# driver_y_convertidor.net
KiCad netlist of a schematic drawn in Altium Designer
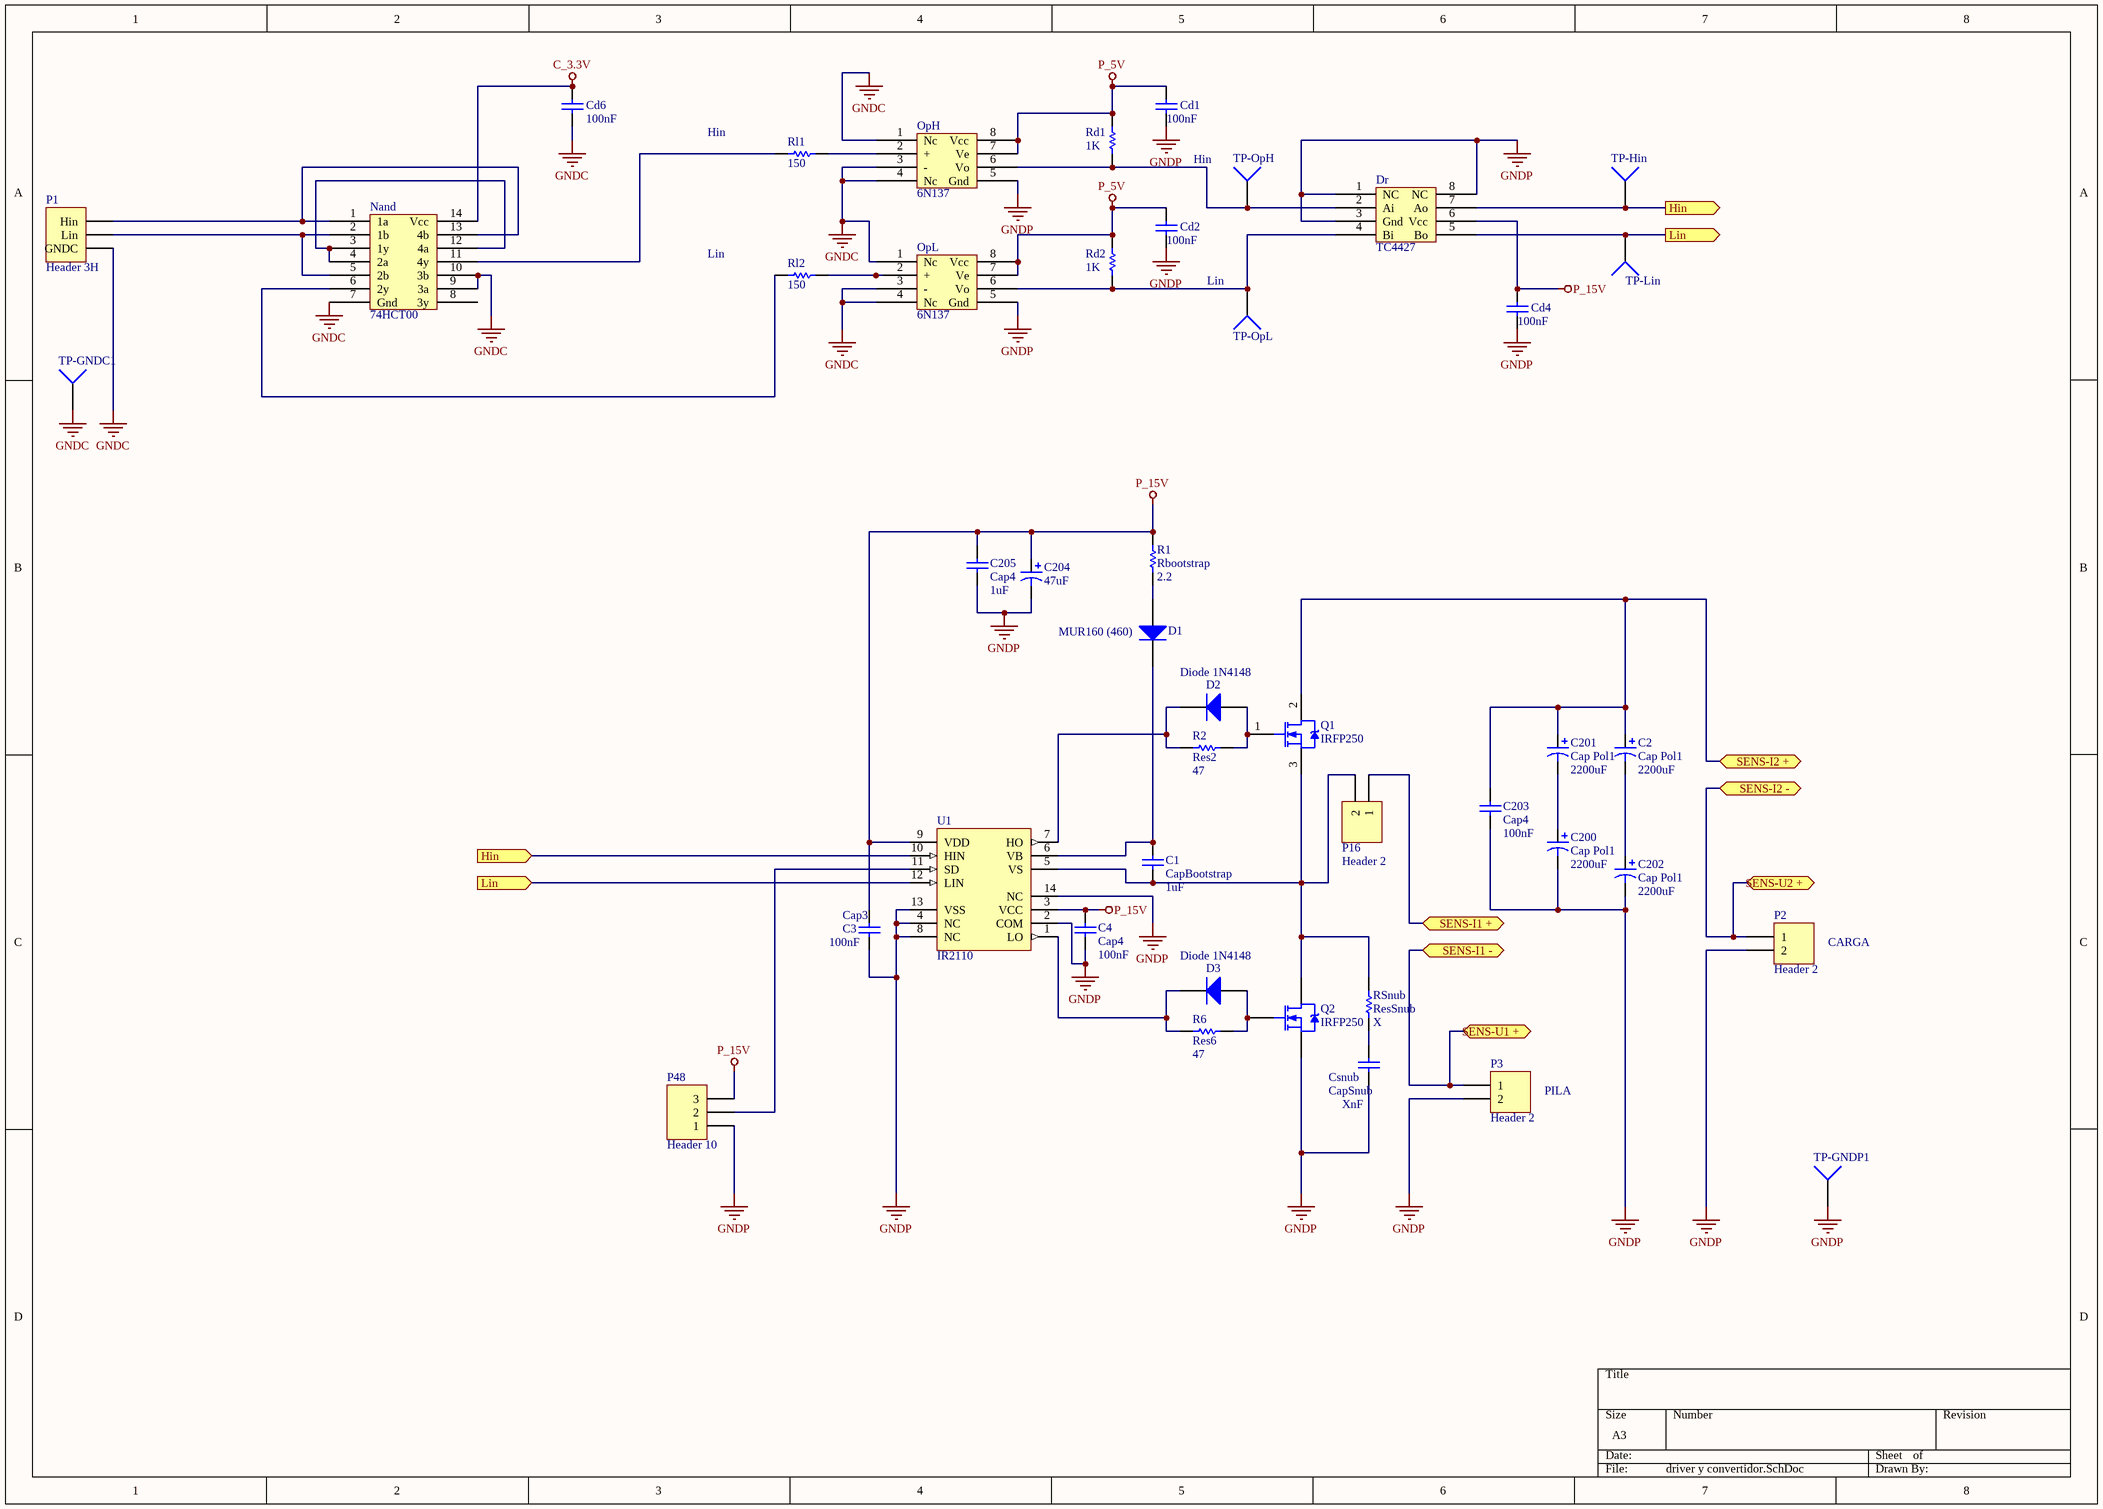
[diagram p0: driver y convertidor.SchDoc]

(export (version "E")
  (design (tool "Eeschema 10.0.6"))
  (components
    (comp (ref "C1")
      (value "CapBootstrap")
      (footprint "RAD-0.1")
      (description "THRU MULTICAPA 50V")
      (fields (field (name "ALTIUM_VALUE") "1uF") (field (name "PUBLISHER") "Altium Limited"))
      (libsource (lib "Miscellaneous Devices") (part "Cap"))
    )
    (comp (ref "C2")
      (value "Cap Pol1")
      (footprint "RB12.7-25*")
      (description "Polarized Capacitor (Radial)")
      (fields (field (name "ALTIUM_VALUE") "2200uF") (field (name "PUBLISHER") "Altium Limited"))
      (libsource (lib "Miscellaneous Devices") (part "Cap Pol1"))
    )
    (comp (ref "C3")
      (value "Cap3")
      (footprint "8-1206")
      (description "SMD MULTICAPA 50V")
      (fields (field (name "ALTIUM_VALUE") "100nF") (field (name "PUBLISHER") "Altium Limited"))
      (libsource (lib "Miscellaneous Devices") (part "Cap"))
    )
    (comp (ref "C4")
      (value "Cap4")
      (footprint "8-1206")
      (description "SMD MULTICAPA 50V")
      (fields (field (name "ALTIUM_VALUE") "100nF") (field (name "PUBLISHER") "Altium Limited"))
      (libsource (lib "Miscellaneous Devices") (part "Cap"))
    )
    (comp (ref "C200")
      (value "Cap Pol1")
      (footprint "RB12.7-25*")
      (description "Polarized Capacitor (Radial)")
      (fields (field (name "ALTIUM_VALUE") "2200uF") (field (name "PUBLISHER") "Altium Limited"))
      (libsource (lib "Miscellaneous Devices") (part "Cap Pol1"))
    )
    (comp (ref "C201")
      (value "Cap Pol1")
      (footprint "RB12.7-25*")
      (description "Polarized Capacitor (Radial)")
      (fields (field (name "ALTIUM_VALUE") "2200uF") (field (name "PUBLISHER") "Altium Limited"))
      (libsource (lib "Miscellaneous Devices") (part "Cap Pol1"))
    )
    (comp (ref "C202")
      (value "Cap Pol1")
      (footprint "RB12.7-25*")
      (description "Polarized Capacitor (Radial)")
      (fields (field (name "ALTIUM_VALUE") "2200uF") (field (name "PUBLISHER") "Altium Limited"))
      (libsource (lib "Miscellaneous Devices") (part "Cap Pol1"))
    )
    (comp (ref "C203")
      (value "Cap4")
      (footprint "8-1206")
      (description "SMD MULTICAPA 50V")
      (fields (field (name "ALTIUM_VALUE") "100nF") (field (name "PUBLISHER") "Altium Limited"))
      (libsource (lib "Miscellaneous Devices") (part "Cap"))
    )
    (comp (ref "C204")
      (value "47uF")
      (footprint "RB5.8-6.4*")
      (description "Polarized Capacitor (Radial)")
      (fields (field (name "Comment") "Cap Pol1") (field (name "PUBLISHER") "Altium Limited"))
      (libsource (lib "Miscellaneous Devices") (part "Cap Pol1"))
    )
    (comp (ref "C205")
      (value "Cap4")
      (footprint "8-1206")
      (description "SMD MULTICAPA 50V")
      (fields (field (name "ALTIUM_VALUE") "1uF") (field (name "PUBLISHER") "Altium Limited"))
      (libsource (lib "Miscellaneous Devices") (part "Cap"))
    )
    (comp (ref "Cd1")
      (value "100nF")
      (footprint "8-1206")
      (description "SMD MULTICAPA 50V")
      (fields (field (name "Comment") "Capd1") (field (name "PUBLISHER") "Altium Limited"))
      (libsource (lib "Miscellaneous Devices") (part "Cap"))
    )
    (comp (ref "Cd2")
      (value "100nF")
      (footprint "8-1206")
      (description "SMD MULTICAPA 50V")
      (fields (field (name "Comment") "Capd2") (field (name "PUBLISHER") "Altium Limited"))
      (libsource (lib "Miscellaneous Devices") (part "Cap"))
    )
    (comp (ref "Cd4")
      (value "100nF")
      (footprint "8-1206")
      (description "SMD MULTICAPA 50V")
      (fields (field (name "Comment") "Capd2") (field (name "PUBLISHER") "Altium Limited"))
      (libsource (lib "Miscellaneous Devices") (part "Cap"))
    )
    (comp (ref "Cd6")
      (value "100nF")
      (footprint "8-1206")
      (description "SMD MULTICAPA 50V")
      (fields (field (name "Comment") "Capd2") (field (name "PUBLISHER") "Altium Limited"))
      (libsource (lib "Miscellaneous Devices") (part "Cap"))
    )
    (comp (ref "Csnub")
      (value "CapSnub")
      (footprint "FootSnub")
      (description "SMD MULTICAPA 50V")
      (fields (field (name "ALTIUM_VALUE") "XnF") (field (name "PUBLISHER") "Altium Limited"))
      (libsource (lib "Miscellaneous Devices") (part "Cap"))
    )
    (comp (ref "D1")
      (value "MUR160 (460)")
      (footprint "CASE 267*")
      (description "THRU")
      (fields (field (name "PUBLISHER") "Altium Limited"))
      (libsource (lib "Miscellaneous Devices") (part "Diode 1N4007"))
    )
    (comp (ref "D2")
      (value "Diode 1N4148")
      (footprint "DO-35")
      (description "THRU")
      (fields (field (name "PUBLISHER") "Altium Limited"))
      (libsource (lib "Miscellaneous Devices") (part "Diode 1N4148"))
    )
    (comp (ref "D3")
      (value "Diode 1N4148")
      (footprint "DO-35")
      (description "THRU")
      (fields (field (name "PUBLISHER") "Altium Limited"))
      (libsource (lib "Miscellaneous Devices") (part "Diode 1N4148"))
    )
    (comp (ref "Dr") (value "TC4427") (footprint "TC4424-DIP8") (libsource (lib "Sensores") (part "TC4427")))
    (comp (ref "Nand")
      (value "74HCT00")
      (footprint "MM74HC00_GON")
      (libsource (lib "Sensores") (part "74HCT00"))
    )
    (comp (ref "OpH") (value "6N137") (footprint "6n137") (libsource (lib "Sensores") (part "6N137")))
    (comp (ref "OpL") (value "6N137") (footprint "6n137") (libsource (lib "Sensores") (part "6N137")))
    (comp (ref "P1")
      (value "Header 3H")
      (footprint "HDR1X3H*")
      (description "Header, 3-Pin, Right Angle")
      (fields (field (name "PUBLISHER") "Altium Limited"))
      (libsource (lib "Miscellaneous Connectors") (part "Header 3H"))
    )
    (comp (ref "P2")
      (value "Header 2")
      (footprint "HDR1X2-POT*")
      (description "Header, 2-Pin")
      (fields (field (name "PUBLISHER") "Altium Limited"))
      (libsource (lib "Miscellaneous Connectors") (part "Header 2"))
    )
    (comp (ref "P3")
      (value "Header 2")
      (footprint "Ind-Conector")
      (description "Header, 2-Pin")
      (fields (field (name "PUBLISHER") "Altium Limited"))
      (libsource (lib "Miscellaneous Connectors") (part "Header 2"))
    )
    (comp (ref "P16")
      (value "Header 2")
      (footprint "Ind-Conector")
      (description "Header, 2-Pin")
      (fields (field (name "PUBLISHER") "Altium Limited"))
      (libsource (lib "") (part "Header 2_1"))
    )
    (comp (ref "P48")
      (value "Header 10")
      (footprint "HDR1X3*")
      (description "Header, 3-Pin")
      (fields (field (name "PUBLISHER") "Altium Limited"))
      (libsource (lib "Miscellaneous Connectors") (part "Header 3"))
    )
    (comp (ref "Q1")
      (value "IRFP250")
      (footprint "TO-247AC")
      (description "HEXFET Power MOSFET")
      (fields (field (name "PUBLISHER") "Altium Limited"))
      (libsource (lib "") (part "IRFP250_1"))
    )
    (comp (ref "Q2")
      (value "IRFP250")
      (footprint "TO-247AC")
      (description "HEXFET Power MOSFET")
      (fields (field (name "PUBLISHER") "Altium Limited"))
      (libsource (lib "IR Discrete MOSFET - Power") (part "IRFP250"))
    )
    (comp (ref "R1")
      (value "Rbootstrap")
      (footprint "8-1206")
      (description "SMD 1206")
      (fields (field (name "ALTIUM_VALUE") "2.2") (field (name "PUBLISHER") "Altium Limited"))
      (libsource (lib "Miscellaneous Devices") (part "Res1"))
    )
    (comp (ref "R2")
      (value "Res2")
      (footprint "8-1206")
      (description "SMD 1206")
      (fields (field (name "ALTIUM_VALUE") "47") (field (name "PUBLISHER") "Altium Limited"))
      (libsource (lib "Miscellaneous Devices") (part "Res1"))
    )
    (comp (ref "R6")
      (value "Res6")
      (footprint "8-1206")
      (description "SMD 1206")
      (fields (field (name "ALTIUM_VALUE") "47") (field (name "PUBLISHER") "Altium Limited"))
      (libsource (lib "Miscellaneous Devices") (part "Res1"))
    )
    (comp (ref "Rd1")
      (value "1K")
      (footprint "8-1206")
      (description "SMD 1206")
      (fields (field (name "Comment") "Rd1") (field (name "PUBLISHER") "Altium Limited"))
      (libsource (lib "Miscellaneous Devices") (part "Res1"))
    )
    (comp (ref "Rd2")
      (value "1K")
      (footprint "8-1206")
      (description "SMD 1206")
      (fields (field (name "Comment") "Rd2") (field (name "PUBLISHER") "Altium Limited"))
      (libsource (lib "Miscellaneous Devices") (part "Res1"))
    )
    (comp (ref "Rl1")
      (value "150")
      (footprint "8-1206")
      (description "SMD 1206")
      (fields (field (name "Comment") "Rd1") (field (name "PUBLISHER") "Altium Limited"))
      (libsource (lib "Miscellaneous Devices") (part "Res1"))
    )
    (comp (ref "Rl2")
      (value "150")
      (footprint "8-1206")
      (description "SMD 1206")
      (fields (field (name "Comment") "Rd1") (field (name "PUBLISHER") "Altium Limited"))
      (libsource (lib "Miscellaneous Devices") (part "Res1"))
    )
    (comp (ref "RSnub")
      (value "ResSnub")
      (footprint "FootSnub")
      (description "SMD 1206")
      (fields (field (name "ALTIUM_VALUE") "X") (field (name "PUBLISHER") "Altium Limited"))
      (libsource (lib "Miscellaneous Devices") (part "Res1"))
    )
    (comp (ref "TP-GNDC1")
      (value "~")
      (footprint "PIN1")
      (description "Socket")
      (fields (field (name "PUBLISHER") "Altium Limited"))
      (libsource (lib "Miscellaneous Connectors") (part "Socket"))
    )
    (comp (ref "TP-GNDP1")
      (value "~")
      (footprint "PIN1")
      (description "Socket")
      (fields (field (name "PUBLISHER") "Altium Limited"))
      (libsource (lib "Miscellaneous Connectors") (part "Socket"))
    )
    (comp (ref "TP-Hin")
      (value "~")
      (footprint "PIN1")
      (description "Socket")
      (fields (field (name "PUBLISHER") "Altium Limited"))
      (libsource (lib "Miscellaneous Connectors") (part "Socket"))
    )
    (comp (ref "TP-Lin")
      (value "~")
      (footprint "PIN1")
      (description "Socket")
      (fields (field (name "PUBLISHER") "Altium Limited"))
      (libsource (lib "Miscellaneous Connectors") (part "Socket"))
    )
    (comp (ref "TP-OpH")
      (value "~")
      (footprint "PIN1")
      (description "Socket")
      (fields (field (name "PUBLISHER") "Altium Limited"))
      (libsource (lib "Miscellaneous Connectors") (part "Socket"))
    )
    (comp (ref "TP-OpL")
      (value "~")
      (footprint "PIN1")
      (description "Socket")
      (fields (field (name "PUBLISHER") "Altium Limited"))
      (libsource (lib "Miscellaneous Connectors") (part "Socket"))
    )
    (comp (ref "U1")
      (value "IR2110")
      (footprint "PDIP14")
      (description "High and Low Side Driver")
      (fields (field (name "PUBLISHER") "Altium Limited"))
      (libsource (lib "IR Interface Bridge Driver") (part "IR2110"))
    )
  )
  (nets
    (net (code "1") (name "/Hin") (class "Default")
      (node (ref "Dr") (pin "7") (pinfunction "Ao_7") (pintype "passive"))
      (node (ref "TP-Hin") (pin "1") (pinfunction "1_1") (pintype "passive"))
      (node (ref "U1") (pin "10") (pinfunction "HIN_10") (pintype "input"))
    )
    (net (code "2") (name "/Lin") (class "Default")
      (node (ref "Dr") (pin "5") (pinfunction "Bo_5") (pintype "passive"))
      (node (ref "TP-Lin") (pin "1") (pinfunction "1_1") (pintype "passive"))
      (node (ref "U1") (pin "12") (pinfunction "LIN_12") (pintype "input"))
    )
    (net (code "3") (name "/SENS-I1 +") (class "Default")
      (node (ref "P16") (pin "1") (pinfunction "1_1") (pintype "passive"))
    )
    (net (code "4") (name "/SENS-I1 -") (class "Default")
      (node (ref "P3") (pin "1") (pinfunction "1_1") (pintype "passive"))
    )
    (net (code "5") (name "/SENS-I2 +") (class "Default")
      (node (ref "C2") (pin "1") (pinfunction "1_1") (pintype "passive"))
      (node (ref "C201") (pin "1") (pinfunction "1_1") (pintype "passive"))
      (node (ref "C203") (pin "1") (pinfunction "1_1") (pintype "passive"))
      (node (ref "Q1") (pin "2") (pinfunction "D_2") (pintype "passive"))
    )
    (net (code "6") (name "/SENS-I2 -") (class "Default")
      (node (ref "P2") (pin "1") (pinfunction "1_1") (pintype "passive"))
    )
    (net (code "7") (name "C_3.3V") (class "Default")
      (node (ref "Cd6") (pin "1") (pinfunction "1_1") (pintype "passive"))
      (node (ref "Nand") (pin "14") (pinfunction "Vcc_14") (pintype "passive"))
    )
    (net (code "8") (name "GNDC") (class "Default")
      (node (ref "Cd6") (pin "2") (pinfunction "2_2") (pintype "passive"))
      (node (ref "Nand") (pin "10") (pinfunction "3b_10") (pintype "passive"))
      (node (ref "Nand") (pin "7") (pinfunction "Gnd_7") (pintype "passive"))
      (node (ref "Nand") (pin "9") (pinfunction "3a_9") (pintype "passive"))
      (node (ref "OpH") (pin "1") (pinfunction "Nc_1") (pintype "passive"))
      (node (ref "OpH") (pin "3") (pinfunction "-_3") (pintype "passive"))
      (node (ref "OpH") (pin "4") (pinfunction "Nc_4") (pintype "passive"))
      (node (ref "OpL") (pin "1") (pinfunction "Nc_1") (pintype "passive"))
      (node (ref "OpL") (pin "3") (pinfunction "-_3") (pintype "passive"))
      (node (ref "OpL") (pin "4") (pinfunction "Nc_4") (pintype "passive"))
      (node (ref "P1") (pin "1") (pinfunction "GNDC_1") (pintype "passive"))
      (node (ref "TP-GNDC1") (pin "1") (pinfunction "1_1") (pintype "passive"))
    )
    (net (code "9") (name "GNDP") (class "Default")
      (node (ref "C200") (pin "2") (pinfunction "2_2") (pintype "passive"))
      (node (ref "C202") (pin "2") (pinfunction "2_2") (pintype "passive"))
      (node (ref "C203") (pin "2") (pinfunction "2_2") (pintype "passive"))
      (node (ref "C204") (pin "2") (pinfunction "2_2") (pintype "passive"))
      (node (ref "C205") (pin "2") (pinfunction "2_2") (pintype "passive"))
      (node (ref "C3") (pin "2") (pinfunction "2_2") (pintype "passive"))
      (node (ref "C4") (pin "2") (pinfunction "2_2") (pintype "passive"))
      (node (ref "Cd1") (pin "2") (pinfunction "2_2") (pintype "passive"))
      (node (ref "Cd2") (pin "2") (pinfunction "2_2") (pintype "passive"))
      (node (ref "Cd4") (pin "2") (pinfunction "2_2") (pintype "passive"))
      (node (ref "Csnub") (pin "2") (pinfunction "2_2") (pintype "passive"))
      (node (ref "Dr") (pin "1") (pinfunction "NC_1") (pintype "passive"))
      (node (ref "Dr") (pin "3") (pinfunction "Gnd_3") (pintype "passive"))
      (node (ref "Dr") (pin "8") (pinfunction "NC_8") (pintype "passive"))
      (node (ref "OpH") (pin "5") (pinfunction "Gnd_5") (pintype "passive"))
      (node (ref "OpL") (pin "5") (pinfunction "Gnd_5") (pintype "passive"))
      (node (ref "P2") (pin "2") (pinfunction "2_2") (pintype "passive"))
      (node (ref "P3") (pin "2") (pinfunction "2_2") (pintype "passive"))
      (node (ref "P48") (pin "1") (pinfunction "1_1") (pintype "passive"))
      (node (ref "Q2") (pin "3") (pinfunction "S_3") (pintype "passive"))
      (node (ref "TP-GNDP1") (pin "1") (pinfunction "1_1") (pintype "passive"))
      (node (ref "U1") (pin "13") (pinfunction "VSS_13") (pintype "power_in"))
      (node (ref "U1") (pin "14") (pinfunction "NC_14") (pintype "passive"))
      (node (ref "U1") (pin "2") (pinfunction "COM_2") (pintype "power_in"))
      (node (ref "U1") (pin "4") (pinfunction "NC_4") (pintype "passive"))
      (node (ref "U1") (pin "8") (pinfunction "NC_8") (pintype "passive"))
    )
    (net (code "10") (name "Net-(C2-Pad2)") (class "Default")
      (node (ref "C2") (pin "2") (pinfunction "2_2") (pintype "passive"))
      (node (ref "C202") (pin "1") (pinfunction "1_1") (pintype "passive"))
    )
    (net (code "11") (name "Net-(C200-Pad1)") (class "Default")
      (node (ref "C200") (pin "1") (pinfunction "1_1") (pintype "passive"))
      (node (ref "C201") (pin "2") (pinfunction "2_2") (pintype "passive"))
    )
    (net (code "12") (name "Net-(Csnub-Pad1)") (class "Default")
      (node (ref "Csnub") (pin "1") (pinfunction "1_1") (pintype "passive"))
      (node (ref "RSnub") (pin "1") (pinfunction "1_1") (pintype "passive"))
    )
    (net (code "13") (name "Net-(D1-A)") (class "Default")
      (node (ref "D1") (pin "1") (pinfunction "A_1") (pintype "passive"))
      (node (ref "R1") (pin "2") (pinfunction "2_2") (pintype "passive"))
    )
    (net (code "14") (name "Net-(D1-K)") (class "Default")
      (node (ref "C1") (pin "1") (pinfunction "1_1") (pintype "passive"))
      (node (ref "D1") (pin "2") (pinfunction "K_2") (pintype "passive"))
      (node (ref "U1") (pin "6") (pinfunction "VB_6") (pintype "power_in"))
    )
    (net (code "15") (name "Net-(D2-A)") (class "Default")
      (node (ref "D2") (pin "1") (pinfunction "A_1") (pintype "passive"))
      (node (ref "Q1") (pin "1") (pinfunction "G_1") (pintype "passive"))
      (node (ref "R2") (pin "2") (pinfunction "2_2") (pintype "passive"))
    )
    (net (code "16") (name "Net-(D2-K)") (class "Default")
      (node (ref "D2") (pin "2") (pinfunction "K_2") (pintype "passive"))
      (node (ref "R2") (pin "1") (pinfunction "1_1") (pintype "passive"))
      (node (ref "U1") (pin "7") (pinfunction "HO_7") (pintype "output"))
    )
    (net (code "17") (name "Net-(D3-A)") (class "Default")
      (node (ref "D3") (pin "1") (pinfunction "A_1") (pintype "passive"))
      (node (ref "Q2") (pin "1") (pinfunction "G_1") (pintype "passive"))
      (node (ref "R6") (pin "2") (pinfunction "2_2") (pintype "passive"))
    )
    (net (code "18") (name "Net-(D3-K)") (class "Default")
      (node (ref "D3") (pin "2") (pinfunction "K_2") (pintype "passive"))
      (node (ref "R6") (pin "1") (pinfunction "1_1") (pintype "passive"))
      (node (ref "U1") (pin "1") (pinfunction "LO_1") (pintype "output"))
    )
    (net (code "19") (name "Net-(Dr-Ai)") (class "Default")
      (node (ref "Dr") (pin "2") (pinfunction "Ai_2") (pintype "passive"))
      (node (ref "OpH") (pin "6") (pinfunction "Vo_6") (pintype "passive"))
      (node (ref "Rd1") (pin "2") (pinfunction "2_2") (pintype "passive"))
      (node (ref "TP-OpH") (pin "1") (pinfunction "1_1") (pintype "passive"))
    )
    (net (code "20") (name "Net-(Dr-Bi)") (class "Default")
      (node (ref "Dr") (pin "4") (pinfunction "Bi_4") (pintype "passive"))
      (node (ref "OpL") (pin "6") (pinfunction "Vo_6") (pintype "passive"))
      (node (ref "Rd2") (pin "2") (pinfunction "2_2") (pintype "passive"))
      (node (ref "TP-OpL") (pin "1") (pinfunction "1_1") (pintype "passive"))
    )
    (net (code "21") (name "Net-(Nand-1a)") (class "Default")
      (node (ref "Nand") (pin "1") (pinfunction "1a_1") (pintype "passive"))
      (node (ref "Nand") (pin "13") (pinfunction "4b_13") (pintype "passive"))
      (node (ref "P1") (pin "3") (pinfunction "Hin_3") (pintype "passive"))
    )
    (net (code "22") (name "Net-(Nand-1b)") (class "Default")
      (node (ref "Nand") (pin "2") (pinfunction "1b_2") (pintype "passive"))
      (node (ref "Nand") (pin "5") (pinfunction "2b_5") (pintype "passive"))
      (node (ref "P1") (pin "2") (pinfunction "Lin_2") (pintype "passive"))
    )
    (net (code "23") (name "Net-(Nand-1y)") (class "Default")
      (node (ref "Nand") (pin "12") (pinfunction "4a_12") (pintype "passive"))
      (node (ref "Nand") (pin "3") (pinfunction "1y_3") (pintype "passive"))
      (node (ref "Nand") (pin "4") (pinfunction "2a_4") (pintype "passive"))
    )
    (net (code "24") (name "Net-(Nand-2y)") (class "Default")
      (node (ref "Nand") (pin "6") (pinfunction "2y_6") (pintype "passive"))
      (node (ref "Rl2") (pin "1") (pinfunction "1_1") (pintype "passive"))
    )
    (net (code "25") (name "Net-(Nand-4y)") (class "Default")
      (node (ref "Nand") (pin "11") (pinfunction "4y_11") (pintype "passive"))
      (node (ref "Rl1") (pin "1") (pinfunction "1_1") (pintype "passive"))
    )
    (net (code "26") (name "Net-(OpH-+)") (class "Default")
      (node (ref "OpH") (pin "2") (pinfunction "+_2") (pintype "passive"))
      (node (ref "Rl1") (pin "2") (pinfunction "2_2") (pintype "passive"))
    )
    (net (code "27") (name "Net-(OpL-+)") (class "Default")
      (node (ref "OpL") (pin "2") (pinfunction "+_2") (pintype "passive"))
      (node (ref "Rl2") (pin "2") (pinfunction "2_2") (pintype "passive"))
    )
    (net (code "28") (name "Net-(Q1-S)") (class "Default")
      (node (ref "C1") (pin "2") (pinfunction "2_2") (pintype "passive"))
      (node (ref "P16") (pin "2") (pinfunction "2_2") (pintype "passive"))
      (node (ref "Q1") (pin "3") (pinfunction "S_3") (pintype "passive"))
      (node (ref "Q2") (pin "2") (pinfunction "D_2") (pintype "passive"))
      (node (ref "RSnub") (pin "2") (pinfunction "2_2") (pintype "passive"))
      (node (ref "U1") (pin "5") (pinfunction "VS_5") (pintype "power_in"))
    )
    (net (code "29") (name "Net-(U1-SD)") (class "Default")
      (node (ref "P48") (pin "2") (pinfunction "2_2") (pintype "passive"))
      (node (ref "U1") (pin "11") (pinfunction "SD_11") (pintype "input"))
    )
    (net (code "30") (name "P_5V") (class "Default")
      (node (ref "Cd1") (pin "1") (pinfunction "1_1") (pintype "passive"))
      (node (ref "Cd2") (pin "1") (pinfunction "1_1") (pintype "passive"))
      (node (ref "OpH") (pin "7") (pinfunction "Ve_7") (pintype "passive"))
      (node (ref "OpH") (pin "8") (pinfunction "Vcc_8") (pintype "passive"))
      (node (ref "OpL") (pin "7") (pinfunction "Ve_7") (pintype "passive"))
      (node (ref "OpL") (pin "8") (pinfunction "Vcc_8") (pintype "passive"))
      (node (ref "Rd1") (pin "1") (pinfunction "1_1") (pintype "passive"))
      (node (ref "Rd2") (pin "1") (pinfunction "1_1") (pintype "passive"))
    )
    (net (code "31") (name "P_15V") (class "Default")
      (node (ref "C204") (pin "1") (pinfunction "1_1") (pintype "passive"))
      (node (ref "C205") (pin "1") (pinfunction "1_1") (pintype "passive"))
      (node (ref "C3") (pin "1") (pinfunction "1_1") (pintype "passive"))
      (node (ref "C4") (pin "1") (pinfunction "1_1") (pintype "passive"))
      (node (ref "Cd4") (pin "1") (pinfunction "1_1") (pintype "passive"))
      (node (ref "Dr") (pin "6") (pinfunction "Vcc_6") (pintype "passive"))
      (node (ref "P48") (pin "3") (pinfunction "3_3") (pintype "passive"))
      (node (ref "R1") (pin "1") (pinfunction "1_1") (pintype "passive"))
      (node (ref "U1") (pin "3") (pinfunction "VCC_3") (pintype "power_in"))
      (node (ref "U1") (pin "9") (pinfunction "VDD_9") (pintype "power_in"))
    )
    (net (code "32") (name "unconnected-(Nand-3y-Pad8)") (class "Default")
      (node (ref "Nand") (pin "8") (pinfunction "3y_8") (pintype "passive"))
    )
  )
)
